# cpm_mikrobus.net
KiCad netlist of a schematic drawn in EAGLE
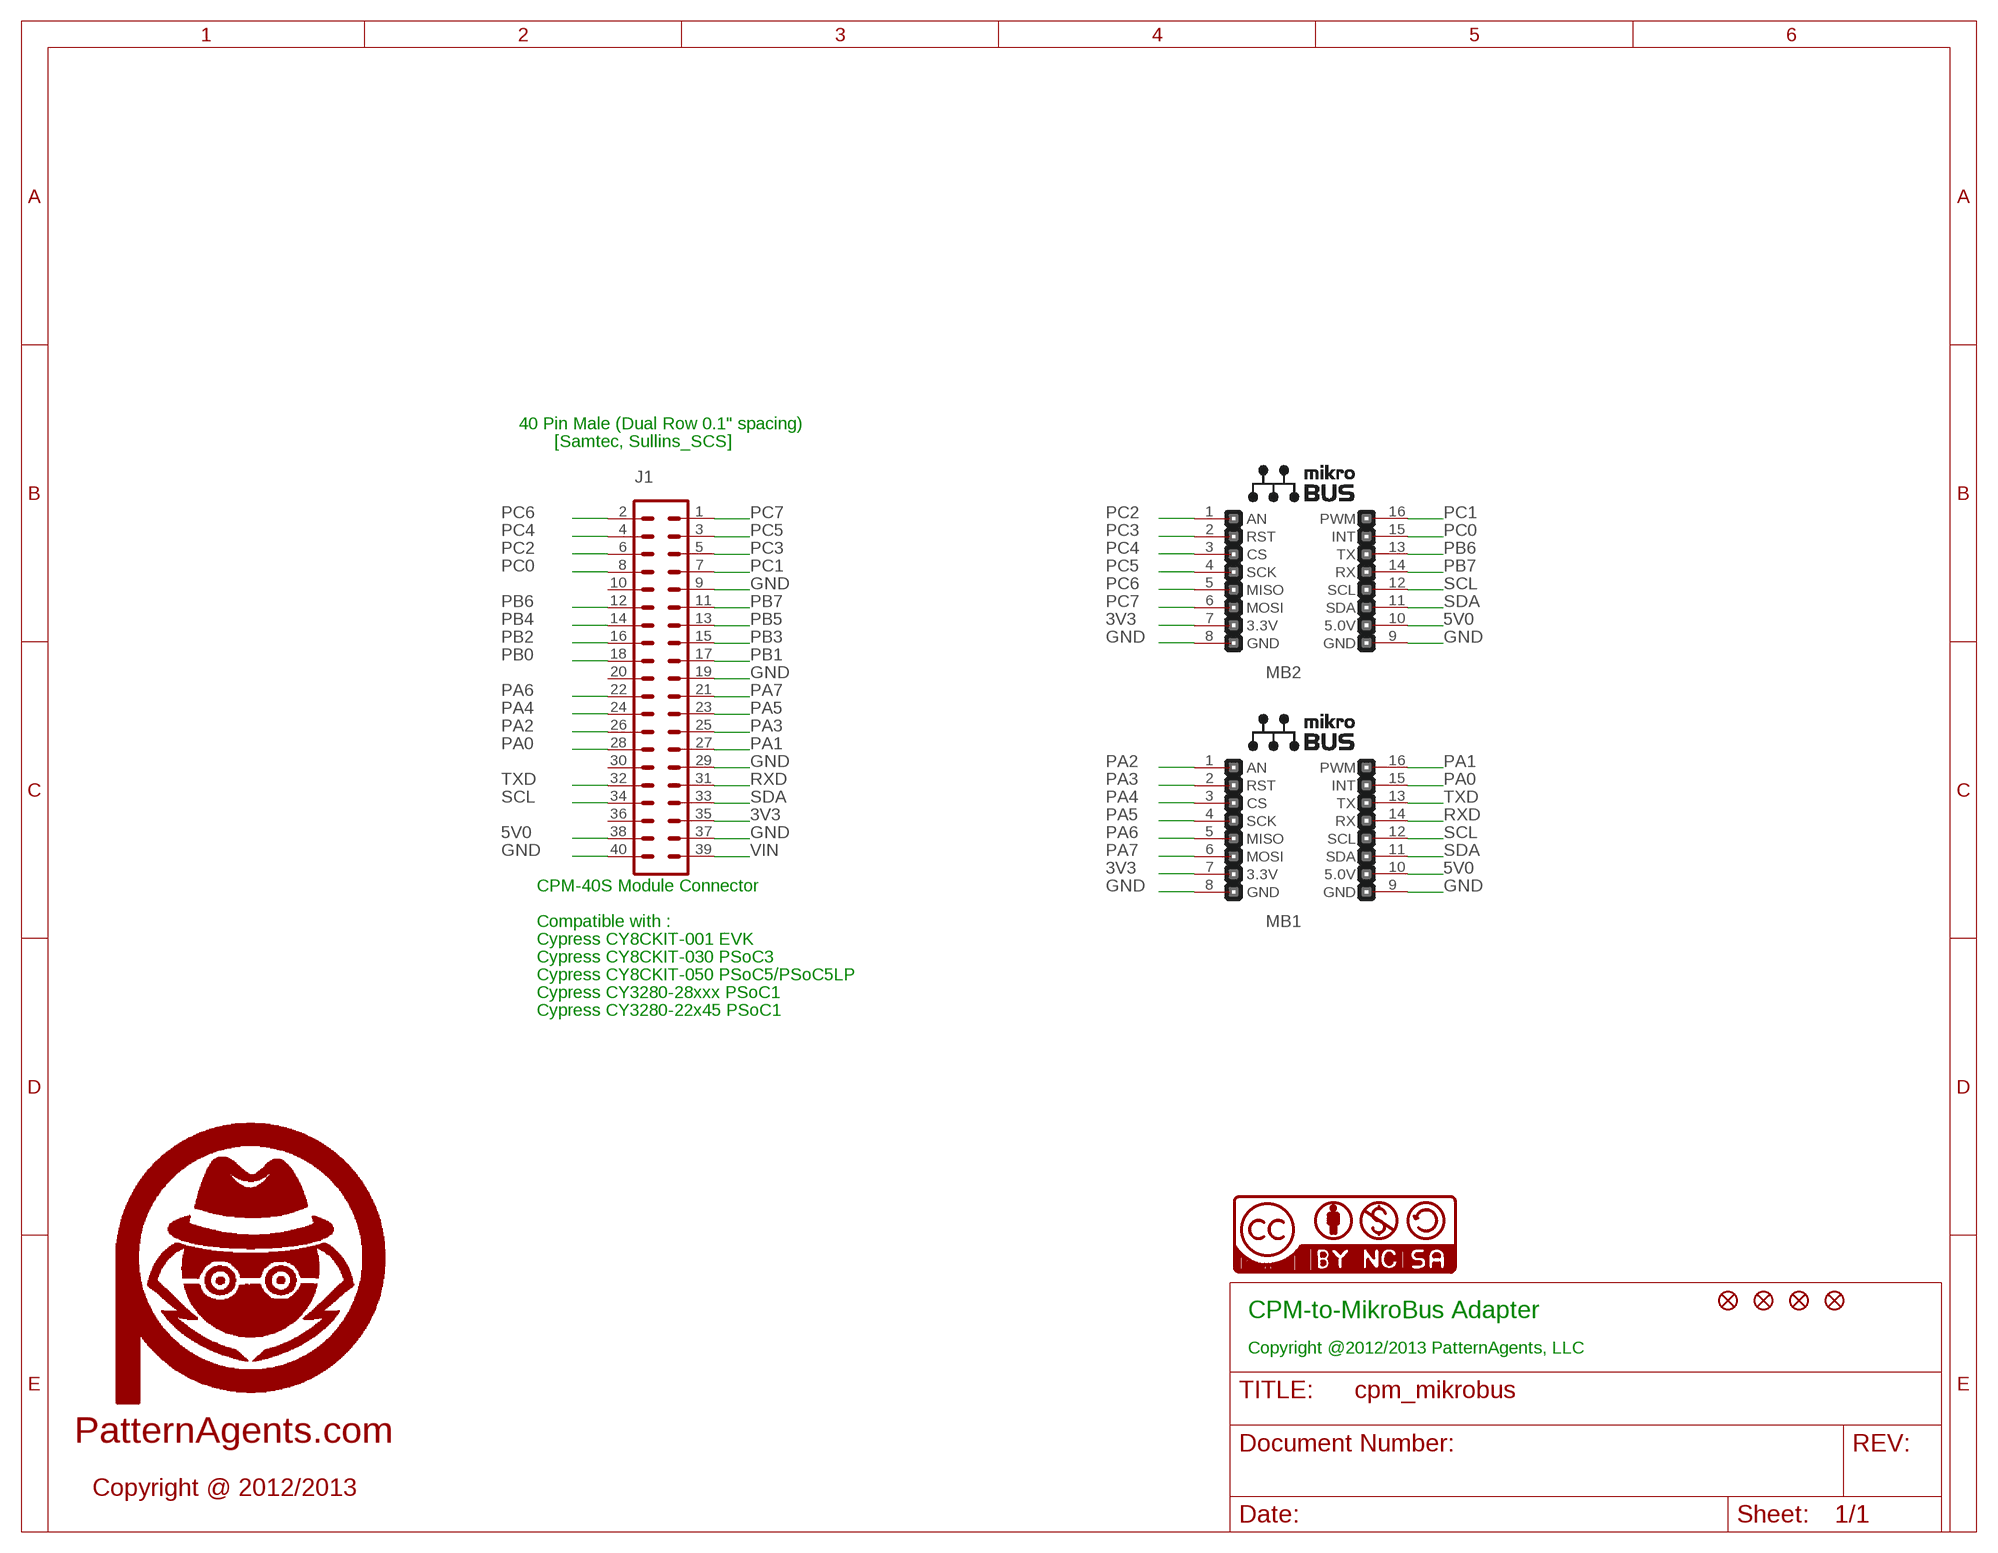
[diagram p0: schematic, sheet 1]

(export (version "E")
  (design (tool "Eeschema 10.0.6"))
  (components
    (comp (ref "J1")
      (value "SULLINS_SCS")
      (footprint "eagle-import:MA20-2")
      (fields (field (name "MF") "Sullins") (field (name "MPN") "PBC20DBAN"))
      (libsource (lib "eagle-import") (part "MA20-2"))
    )
    (comp (ref "JP1")
      (value "FIDUCIAL1.5X3")
      (footprint "eagle-import:FIDUCIAL-1.5X3")
      (libsource (lib "eagle-import") (part "FIDUCIAL1.5X3"))
    )
    (comp (ref "JP2")
      (value "FIDUCIAL1.5X3")
      (footprint "eagle-import:FIDUCIAL-1.5X3")
      (libsource (lib "eagle-import") (part "FIDUCIAL1.5X3"))
    )
    (comp (ref "JP3")
      (value "FIDUCIAL1.5X3")
      (footprint "eagle-import:FIDUCIAL-1.5X3")
      (libsource (lib "eagle-import") (part "FIDUCIAL1.5X3"))
    )
    (comp (ref "JP4")
      (value "FIDUCIAL1.5X3")
      (footprint "eagle-import:FIDUCIAL-1.5X3")
      (libsource (lib "eagle-import") (part "FIDUCIAL1.5X3"))
    )
    (comp (ref "MB1")
      (value "MIKROBUS_SOCKET")
      (footprint "eagle-import:MIKROBUS_SOCKET")
      (libsource (lib "eagle-import") (part "MIKROBUS_SOCKET"))
    )
    (comp (ref "MB2")
      (value "MIKROBUS_SOCKET")
      (footprint "eagle-import:MIKROBUS_SOCKET")
      (libsource (lib "eagle-import") (part "MIKROBUS_SOCKET"))
    )
    (comp (ref "U$1")
      (value "LOGO_PA_AGENTLARGE")
      (footprint "eagle-import:LOGO_PA_AGENT_LARGE")
      (libsource (lib "eagle-import") (part "LOGO_PA_AGENTLARGE"))
    )
    (comp (ref "U$2")
      (value "BY_CC_SA_SYMNULL")
      (footprint "eagle-import:NULL_SYM")
      (libsource (lib "eagle-import") (part "BY_CC_SA_SYMNULL"))
    )
  )
  (nets
    (net (code "1") (name "/3V3") (class "Default")
      (node (ref "J1") (pin "35") (pinfunction "35_35") (pintype "passive"))
      (node (ref "MB1") (pin "7") (pinfunction "3.3V_7") (pintype "power_in"))
      (node (ref "MB2") (pin "7") (pinfunction "3.3V_7") (pintype "power_in"))
    )
    (net (code "2") (name "/5V0") (class "Default")
      (node (ref "J1") (pin "38") (pinfunction "38_38") (pintype "passive"))
      (node (ref "MB1") (pin "10") (pinfunction "5.0V_10") (pintype "power_in"))
      (node (ref "MB2") (pin "10") (pinfunction "5.0V_10") (pintype "power_in"))
    )
    (net (code "3") (name "/GND") (class "Default")
      (node (ref "J1") (pin "19") (pinfunction "19_19") (pintype "passive"))
      (node (ref "J1") (pin "29") (pinfunction "29_29") (pintype "passive"))
      (node (ref "J1") (pin "37") (pinfunction "37_37") (pintype "passive"))
      (node (ref "J1") (pin "40") (pinfunction "40_40") (pintype "passive"))
      (node (ref "J1") (pin "9") (pinfunction "9_9") (pintype "passive"))
      (node (ref "MB1") (pin "8") (pinfunction "GND_8") (pintype "power_in"))
      (node (ref "MB1") (pin "9") (pinfunction "GND_9") (pintype "power_in"))
      (node (ref "MB2") (pin "8") (pinfunction "GND_8") (pintype "power_in"))
      (node (ref "MB2") (pin "9") (pinfunction "GND_9") (pintype "power_in"))
    )
    (net (code "4") (name "/PA0") (class "Default")
      (node (ref "J1") (pin "28") (pinfunction "28_28") (pintype "passive"))
      (node (ref "MB1") (pin "15") (pinfunction "INT_15") (pintype "bidirectional"))
    )
    (net (code "5") (name "/PA1") (class "Default")
      (node (ref "J1") (pin "27") (pinfunction "27_27") (pintype "passive"))
      (node (ref "MB1") (pin "16") (pinfunction "PWM_16") (pintype "bidirectional"))
    )
    (net (code "6") (name "/PA2") (class "Default")
      (node (ref "J1") (pin "26") (pinfunction "26_26") (pintype "passive"))
      (node (ref "MB1") (pin "1") (pinfunction "AN_1") (pintype "bidirectional"))
    )
    (net (code "7") (name "/PA3") (class "Default")
      (node (ref "J1") (pin "25") (pinfunction "25_25") (pintype "passive"))
      (node (ref "MB1") (pin "2") (pinfunction "RST_2") (pintype "bidirectional"))
    )
    (net (code "8") (name "/PA4") (class "Default")
      (node (ref "J1") (pin "24") (pinfunction "24_24") (pintype "passive"))
      (node (ref "MB1") (pin "3") (pinfunction "CS_3") (pintype "bidirectional"))
    )
    (net (code "9") (name "/PA5") (class "Default")
      (node (ref "J1") (pin "23") (pinfunction "23_23") (pintype "passive"))
      (node (ref "MB1") (pin "4") (pinfunction "SCK_4") (pintype "bidirectional"))
    )
    (net (code "10") (name "/PA6") (class "Default")
      (node (ref "J1") (pin "22") (pinfunction "22_22") (pintype "passive"))
      (node (ref "MB1") (pin "5") (pinfunction "MISO_5") (pintype "bidirectional"))
    )
    (net (code "11") (name "/PA7") (class "Default")
      (node (ref "J1") (pin "21") (pinfunction "21_21") (pintype "passive"))
      (node (ref "MB1") (pin "6") (pinfunction "MOSI_6") (pintype "bidirectional"))
    )
    (net (code "12") (name "/PB0") (class "Default")
      (node (ref "J1") (pin "18") (pinfunction "18_18") (pintype "passive"))
    )
    (net (code "13") (name "/PB1") (class "Default")
      (node (ref "J1") (pin "17") (pinfunction "17_17") (pintype "passive"))
    )
    (net (code "14") (name "/PB2") (class "Default")
      (node (ref "J1") (pin "16") (pinfunction "16_16") (pintype "passive"))
    )
    (net (code "15") (name "/PB3") (class "Default")
      (node (ref "J1") (pin "15") (pinfunction "15_15") (pintype "passive"))
    )
    (net (code "16") (name "/PB4") (class "Default")
      (node (ref "J1") (pin "14") (pinfunction "14_14") (pintype "passive"))
    )
    (net (code "17") (name "/PB5") (class "Default")
      (node (ref "J1") (pin "13") (pinfunction "13_13") (pintype "passive"))
    )
    (net (code "18") (name "/PB6") (class "Default")
      (node (ref "J1") (pin "12") (pinfunction "12_12") (pintype "passive"))
      (node (ref "MB2") (pin "13") (pinfunction "TX_13") (pintype "bidirectional"))
    )
    (net (code "19") (name "/PB7") (class "Default")
      (node (ref "J1") (pin "11") (pinfunction "11_11") (pintype "passive"))
      (node (ref "MB2") (pin "14") (pinfunction "RX_14") (pintype "bidirectional"))
    )
    (net (code "20") (name "/PC0") (class "Default")
      (node (ref "J1") (pin "8") (pinfunction "8_8") (pintype "passive"))
      (node (ref "MB2") (pin "15") (pinfunction "INT_15") (pintype "bidirectional"))
    )
    (net (code "21") (name "/PC1") (class "Default")
      (node (ref "J1") (pin "7") (pinfunction "7_7") (pintype "passive"))
      (node (ref "MB2") (pin "16") (pinfunction "PWM_16") (pintype "bidirectional"))
    )
    (net (code "22") (name "/PC2") (class "Default")
      (node (ref "J1") (pin "6") (pinfunction "6_6") (pintype "passive"))
      (node (ref "MB2") (pin "1") (pinfunction "AN_1") (pintype "bidirectional"))
    )
    (net (code "23") (name "/PC3") (class "Default")
      (node (ref "J1") (pin "5") (pinfunction "5_5") (pintype "passive"))
      (node (ref "MB2") (pin "2") (pinfunction "RST_2") (pintype "bidirectional"))
    )
    (net (code "24") (name "/PC4") (class "Default")
      (node (ref "J1") (pin "4") (pinfunction "4_4") (pintype "passive"))
      (node (ref "MB2") (pin "3") (pinfunction "CS_3") (pintype "bidirectional"))
    )
    (net (code "25") (name "/PC5") (class "Default")
      (node (ref "J1") (pin "3") (pinfunction "3_3") (pintype "passive"))
      (node (ref "MB2") (pin "4") (pinfunction "SCK_4") (pintype "bidirectional"))
    )
    (net (code "26") (name "/PC6") (class "Default")
      (node (ref "J1") (pin "2") (pinfunction "2_2") (pintype "passive"))
      (node (ref "MB2") (pin "5") (pinfunction "MISO_5") (pintype "bidirectional"))
    )
    (net (code "27") (name "/PC7") (class "Default")
      (node (ref "J1") (pin "1") (pinfunction "1_1") (pintype "passive"))
      (node (ref "MB2") (pin "6") (pinfunction "MOSI_6") (pintype "bidirectional"))
    )
    (net (code "28") (name "/RXD") (class "Default")
      (node (ref "J1") (pin "31") (pinfunction "31_31") (pintype "passive"))
      (node (ref "MB1") (pin "14") (pinfunction "RX_14") (pintype "bidirectional"))
    )
    (net (code "29") (name "/SCL") (class "Default")
      (node (ref "J1") (pin "34") (pinfunction "34_34") (pintype "passive"))
      (node (ref "MB1") (pin "12") (pinfunction "SCL_12") (pintype "bidirectional"))
      (node (ref "MB2") (pin "12") (pinfunction "SCL_12") (pintype "bidirectional"))
    )
    (net (code "30") (name "/SDA") (class "Default")
      (node (ref "J1") (pin "33") (pinfunction "33_33") (pintype "passive"))
      (node (ref "MB1") (pin "11") (pinfunction "SDA_11") (pintype "bidirectional"))
      (node (ref "MB2") (pin "11") (pinfunction "SDA_11") (pintype "bidirectional"))
    )
    (net (code "31") (name "/TXD") (class "Default")
      (node (ref "J1") (pin "32") (pinfunction "32_32") (pintype "passive"))
      (node (ref "MB1") (pin "13") (pinfunction "TX_13") (pintype "bidirectional"))
    )
    (net (code "32") (name "/VIN") (class "Default")
      (node (ref "J1") (pin "39") (pinfunction "39_39") (pintype "passive"))
    )
    (net (code "33") (name "unconnected-(J1-Pad10)") (class "Default")
      (node (ref "J1") (pin "10") (pinfunction "10_10") (pintype "passive"))
    )
    (net (code "34") (name "unconnected-(J1-Pad20)") (class "Default")
      (node (ref "J1") (pin "20") (pinfunction "20_20") (pintype "passive"))
    )
    (net (code "35") (name "unconnected-(J1-Pad30)") (class "Default")
      (node (ref "J1") (pin "30") (pinfunction "30_30") (pintype "passive"))
    )
    (net (code "36") (name "unconnected-(J1-Pad36)") (class "Default")
      (node (ref "J1") (pin "36") (pinfunction "36_36") (pintype "passive"))
    )
  )
)
